# -_-.net
KiCad netlist of a schematic drawn in Altium Designer
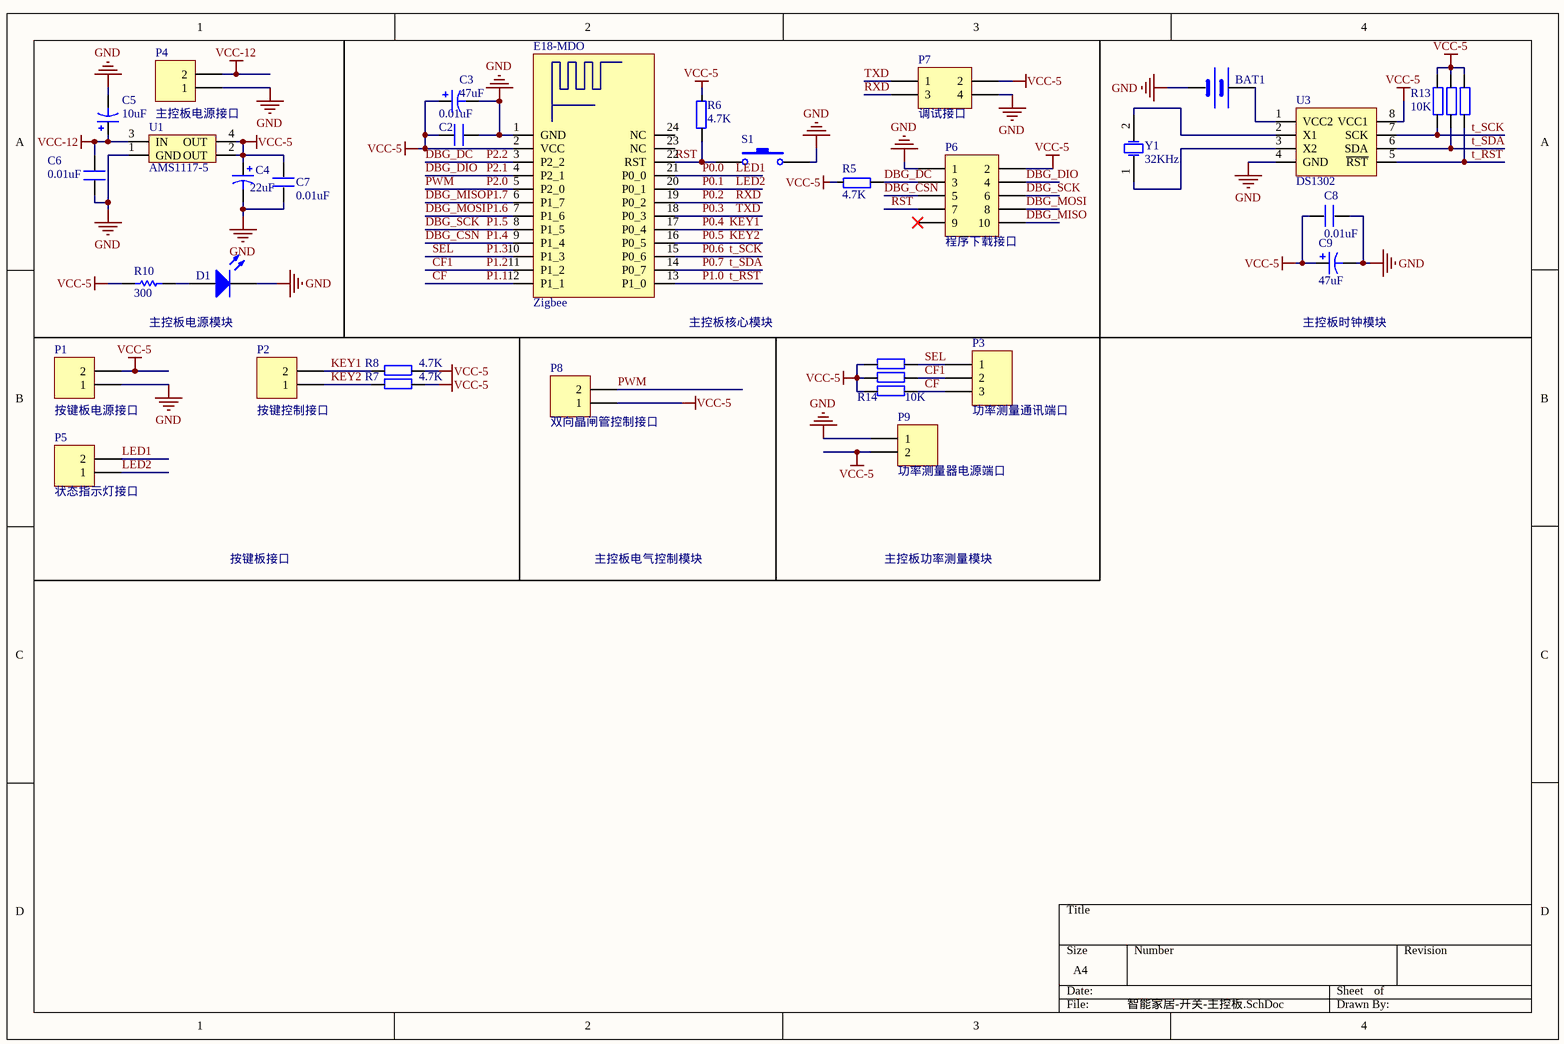
[diagram p0: 智能家居-开关-主控板.SchDoc]

(export (version "E")
  (design (tool "Eeschema 10.0.6"))
  (components
    (comp (ref "BAT1") (value "BATT") (footprint "BATM") (libsource (lib "WARSHIP") (part "BAT")))
    (comp (ref "C2") (value "0.01uF") (footprint "0.1UF") (libsource (lib "WARSHIP") (part "C")))
    (comp (ref "C3")
      (value "47uF")
      (footprint "CD5")
      (description "Polarized Capacitor (Radial)")
      (fields (field (name "Comment") "Cap Pol1") (field (name "PUBLISHER") "Altium Limited"))
      (libsource (lib "Miscellaneous Devices") (part "Cap Pol1"))
    )
    (comp (ref "C4")
      (value "22uF")
      (footprint "CD5")
      (description "Polarized Capacitor (Radial)")
      (fields (field (name "Comment") "Cap Pol1") (field (name "PUBLISHER") "Altium Limited"))
      (libsource (lib "Miscellaneous Devices") (part "Cap Pol1"))
    )
    (comp (ref "C5")
      (value "10uF")
      (footprint "CD5")
      (description "Polarized Capacitor (Radial)")
      (fields (field (name "Comment") "Cap Pol1") (field (name "PUBLISHER") "Altium Limited"))
      (libsource (lib "Miscellaneous Devices") (part "Cap Pol1"))
    )
    (comp (ref "C6") (value "0.01uF") (footprint "0.1UF") (libsource (lib "WARSHIP") (part "C")))
    (comp (ref "C7") (value "0.01uF") (footprint "0.1UF") (libsource (lib "WARSHIP") (part "C")))
    (comp (ref "C8") (value "0.01uF") (footprint "0.1UF") (libsource (lib "WARSHIP") (part "C")))
    (comp (ref "C9")
      (value "47uF")
      (footprint "CD5")
      (description "Polarized Capacitor (Radial)")
      (fields (field (name "Comment") "Cap Pol1") (field (name "PUBLISHER") "Altium Limited"))
      (libsource (lib "Miscellaneous Devices") (part "Cap Pol1"))
    )
    (comp (ref "D1")
      (value "LED0")
      (footprint "LED-3")
      (description "Typical INFRARED GaAs LED")
      (fields (field (name "PUBLISHER") "Altium Limited"))
      (libsource (lib "Miscellaneous Devices") (part "LED0"))
    )
    (comp (ref "E18-MDO")
      (value "Zigbee")
      (footprint "E18-MD0-1")
      (description "Zigbee模块")
      (libsource (lib "ESP8266V1.2") (part "E18-MDO"))
    )
    (comp (ref "P1")
      (value "按键板电源接口")
      (footprint "DG1282")
      (description "Header, 2-Pin, Right Angle")
      (fields (field (name "PUBLISHER") "Altium Limited"))
      (libsource (lib "") (part "Header 2H_1"))
    )
    (comp (ref "P2")
      (value "按键控制接口")
      (footprint "DG1282")
      (description "Header, 2-Pin, Right Angle")
      (fields (field (name "PUBLISHER") "Altium Limited"))
      (libsource (lib "") (part "Header 2H_1"))
    )
    (comp (ref "P3")
      (value "功率测量通讯端口")
      (footprint "DG1283")
      (description "Header, 3-Pin")
      (fields (field (name "PUBLISHER") "Altium Limited"))
      (libsource (lib "Miscellaneous Connectors") (part "Header 3"))
    )
    (comp (ref "P4")
      (value "主控板电源接口")
      (footprint "DG1282")
      (description "Header, 2-Pin, Right Angle")
      (fields (field (name "PUBLISHER") "Altium Limited"))
      (libsource (lib "") (part "Header 2H_1"))
    )
    (comp (ref "P5")
      (value "状态指示灯接口")
      (footprint "DG1282")
      (description "Header, 2-Pin, Right Angle")
      (fields (field (name "PUBLISHER") "Altium Limited"))
      (libsource (lib "") (part "Header 2H_1"))
    )
    (comp (ref "P6")
      (value "程序下载接口")
      (footprint "HDR2X5")
      (description "Header, 5-Pin, Dual row")
      (fields (field (name "PUBLISHER") "Altium Limited"))
      (libsource (lib "Miscellaneous Connectors") (part "Header 5X2"))
    )
    (comp (ref "P7")
      (value "调试接口")
      (footprint "HDR2X2")
      (description "Header, 2-Pin, Dual row, Right Angle")
      (fields (field (name "PUBLISHER") "Altium Limited"))
      (libsource (lib "Miscellaneous Connectors") (part "Header 2X2H"))
    )
    (comp (ref "P8")
      (value "双向晶闸管控制接口")
      (footprint "DG1282")
      (description "Header, 2-Pin, Right Angle")
      (fields (field (name "PUBLISHER") "Altium Limited"))
      (libsource (lib "") (part "Header 2H_1"))
    )
    (comp (ref "P9")
      (value "功率测量器电源端口")
      (footprint "DG1282")
      (description "Header, 2-Pin, Right Angle")
      (fields (field (name "PUBLISHER") "Altium Limited"))
      (libsource (lib "Miscellaneous Connectors") (part "Header 2H"))
    )
    (comp (ref "R5") (value "4.7K") (footprint "AXIAL-0.3") (libsource (lib "ESP8266V1.2") (part "R")))
    (comp (ref "R6") (value "4.7K") (footprint "AXIAL-0.3") (libsource (lib "ESP8266V1.2") (part "R")))
    (comp (ref "R7") (value "4.7K") (footprint "AXIAL-0.3") (libsource (lib "ESP8266V1.2") (part "R")))
    (comp (ref "R8") (value "4.7K") (footprint "AXIAL-0.3") (libsource (lib "ESP8266V1.2") (part "R")))
    (comp (ref "R10")
      (value "300")
      (footprint "AXIAL-0.3")
      (description "Resistor")
      (fields (field (name "Comment") "Res1") (field (name "PUBLISHER") "Altium Limited"))
      (libsource (lib "Miscellaneous Devices") (part "Res1"))
    )
    (comp (ref "R11") (value "10K") (footprint "AXIAL-0.3") (libsource (lib "ESP8266V1.2") (part "R")))
    (comp (ref "R12") (value "10K") (footprint "AXIAL-0.3") (libsource (lib "ESP8266V1.2") (part "R")))
    (comp (ref "R13") (value "10K") (footprint "AXIAL-0.3") (libsource (lib "ESP8266V1.2") (part "R")))
    (comp (ref "R14") (value "10K") (footprint "AXIAL-0.3") (libsource (lib "ESP8266V1.2") (part "R")))
    (comp (ref "R15") (value "10K") (footprint "AXIAL-0.3") (libsource (lib "ESP8266V1.2") (part "R")))
    (comp (ref "R16") (value "10K") (footprint "AXIAL-0.3") (libsource (lib "ESP8266V1.2") (part "R")))
    (comp (ref "S1")
      (value "SW-PB")
      (footprint "KEY_M")
      (description "Switch")
      (fields (field (name "PUBLISHER") "Altium Limited"))
      (libsource (lib "Miscellaneous Devices") (part "SW-PB"))
    )
    (comp (ref "U1") (value "AMS1117-5") (footprint "AMS1117") (libsource (lib "WARSHIP") (part "AMS1117")))
    (comp (ref "U3") (value "DS1302") (footprint "DIP-8N") (libsource (lib "杂项库") (part "DS1302")))
    (comp (ref "Y1")
      (value "32KHz")
      (footprint "3216")
      (description "Crystal Oscillator")
      (fields (field (name "PUBLISHER") "Altium Limited"))
      (libsource (lib "Miscellaneous Devices") (part "XTAL"))
    )
  )
  (nets
    (net (code "1") (name "/CF") (class "Default")
      (node (ref "E18-MDO") (pin "12") (pinfunction "P1_1_12") (pintype "passive"))
      (node (ref "P3") (pin "3") (pinfunction "3_3") (pintype "passive"))
      (node (ref "R14") (pin "1") (pintype "passive"))
    )
    (net (code "2") (name "/CF1") (class "Default")
      (node (ref "E18-MDO") (pin "11") (pinfunction "P1_2_11") (pintype "passive"))
      (node (ref "P3") (pin "2") (pinfunction "2_2") (pintype "passive"))
      (node (ref "R15") (pin "1") (pintype "passive"))
    )
    (net (code "3") (name "/DBG_CSN") (class "Default")
      (node (ref "E18-MDO") (pin "9") (pinfunction "P1_4_9") (pintype "passive"))
      (node (ref "P6") (pin "5") (pinfunction "5_5") (pintype "passive"))
    )
    (net (code "4") (name "/DBG_DC") (class "Default")
      (node (ref "E18-MDO") (pin "3") (pinfunction "P2_2_3") (pintype "passive"))
      (node (ref "P6") (pin "3") (pinfunction "3_3") (pintype "passive"))
      (node (ref "R5") (pin "2") (pintype "passive"))
    )
    (net (code "5") (name "/DBG_DIO") (class "Default")
      (node (ref "E18-MDO") (pin "4") (pinfunction "P2_1_4") (pintype "passive"))
      (node (ref "P6") (pin "4") (pinfunction "4_4") (pintype "passive"))
    )
    (net (code "6") (name "/DBG_MISO") (class "Default")
      (node (ref "E18-MDO") (pin "6") (pinfunction "P1_7_6") (pintype "passive"))
      (node (ref "P6") (pin "10") (pinfunction "10_10") (pintype "passive"))
    )
    (net (code "7") (name "/DBG_MOSI") (class "Default")
      (node (ref "E18-MDO") (pin "7") (pinfunction "P1_6_7") (pintype "passive"))
      (node (ref "P6") (pin "8") (pinfunction "8_8") (pintype "passive"))
    )
    (net (code "8") (name "/DBG_SCK") (class "Default")
      (node (ref "E18-MDO") (pin "8") (pinfunction "P1_5_8") (pintype "passive"))
      (node (ref "P6") (pin "6") (pinfunction "6_6") (pintype "passive"))
    )
    (net (code "9") (name "/KEY1") (class "Default")
      (node (ref "E18-MDO") (pin "17") (pinfunction "P0_4_17") (pintype "passive"))
      (node (ref "P2") (pin "2") (pinfunction "2_2") (pintype "passive"))
      (node (ref "R8") (pin "2") (pintype "passive"))
    )
    (net (code "10") (name "/KEY2") (class "Default")
      (node (ref "E18-MDO") (pin "16") (pinfunction "P0_5_16") (pintype "passive"))
      (node (ref "P2") (pin "1") (pinfunction "1_1") (pintype "passive"))
      (node (ref "R7") (pin "2") (pintype "passive"))
    )
    (net (code "11") (name "/LED1") (class "Default")
      (node (ref "E18-MDO") (pin "21") (pinfunction "P0_0_21") (pintype "passive"))
      (node (ref "P5") (pin "2") (pinfunction "2_2") (pintype "passive"))
    )
    (net (code "12") (name "/LED2") (class "Default")
      (node (ref "E18-MDO") (pin "20") (pinfunction "P0_1_20") (pintype "passive"))
      (node (ref "P5") (pin "1") (pinfunction "1_1") (pintype "passive"))
    )
    (net (code "13") (name "/P0.2") (class "Default")
      (node (ref "E18-MDO") (pin "19") (pinfunction "P0_2_19") (pintype "passive"))
      (node (ref "P7") (pin "3") (pinfunction "3_3") (pintype "passive"))
    )
    (net (code "14") (name "/P0.3") (class "Default")
      (node (ref "E18-MDO") (pin "18") (pinfunction "P0_3_18") (pintype "passive"))
      (node (ref "P7") (pin "1") (pinfunction "1_1") (pintype "passive"))
    )
    (net (code "15") (name "/P0.6") (class "Default")
      (node (ref "E18-MDO") (pin "15") (pinfunction "P0_6_15") (pintype "passive"))
      (node (ref "R13") (pin "1") (pintype "passive"))
      (node (ref "U3") (pin "7") (pinfunction "SCK_7") (pintype "passive"))
    )
    (net (code "16") (name "/P0.7") (class "Default")
      (node (ref "E18-MDO") (pin "14") (pinfunction "P0_7_14") (pintype "passive"))
      (node (ref "R12") (pin "1") (pintype "passive"))
      (node (ref "U3") (pin "6") (pinfunction "SDA_6") (pintype "passive"))
    )
    (net (code "17") (name "/P1.0") (class "Default")
      (node (ref "E18-MDO") (pin "13") (pinfunction "P1_0_13") (pintype "passive"))
      (node (ref "R11") (pin "1") (pintype "passive"))
      (node (ref "U3") (pin "5") (pinfunction "~{RST}_5") (pintype "passive"))
    )
    (net (code "18") (name "/P1.3") (class "Default")
      (node (ref "E18-MDO") (pin "10") (pinfunction "P1_3_10") (pintype "passive"))
      (node (ref "P3") (pin "1") (pinfunction "1_1") (pintype "passive"))
      (node (ref "R16") (pin "1") (pintype "passive"))
    )
    (net (code "19") (name "/P2.0") (class "Default")
      (node (ref "E18-MDO") (pin "5") (pinfunction "P2_0_5") (pintype "passive"))
      (node (ref "P8") (pin "2") (pinfunction "2_2") (pintype "passive"))
    )
    (net (code "20") (name "/RST") (class "Default")
      (node (ref "E18-MDO") (pin "22") (pinfunction "RST_22") (pintype "passive"))
      (node (ref "P6") (pin "7") (pinfunction "7_7") (pintype "passive"))
      (node (ref "R6") (pin "2") (pintype "passive"))
      (node (ref "S1") (pin "1") (pinfunction "1_1") (pintype "passive"))
    )
    (net (code "21") (name "GND") (class "Default")
      (node (ref "BAT1") (pin "2") (pinfunction "GND_2") (pintype "passive"))
      (node (ref "C2") (pin "2") (pintype "passive"))
      (node (ref "C3") (pin "2") (pinfunction "2_2") (pintype "passive"))
      (node (ref "C4") (pin "2") (pinfunction "2_2") (pintype "passive"))
      (node (ref "C5") (pin "2") (pinfunction "2_2") (pintype "passive"))
      (node (ref "C6") (pin "1") (pintype "passive"))
      (node (ref "C7") (pin "1") (pintype "passive"))
      (node (ref "C8") (pin "2") (pintype "passive"))
      (node (ref "C9") (pin "2") (pinfunction "2_2") (pintype "passive"))
      (node (ref "D1") (pin "2") (pinfunction "K_2") (pintype "passive"))
      (node (ref "E18-MDO") (pin "1") (pinfunction "GND_1") (pintype "passive"))
      (node (ref "P1") (pin "1") (pinfunction "1_1") (pintype "passive"))
      (node (ref "P4") (pin "1") (pinfunction "1_1") (pintype "passive"))
      (node (ref "P6") (pin "1") (pinfunction "1_1") (pintype "passive"))
      (node (ref "P7") (pin "4") (pinfunction "4_4") (pintype "passive"))
      (node (ref "P9") (pin "1") (pinfunction "1_1") (pintype "passive"))
      (node (ref "S1") (pin "2") (pinfunction "2_2") (pintype "passive"))
      (node (ref "U1") (pin "1") (pinfunction "GND_1") (pintype "passive"))
      (node (ref "U3") (pin "4") (pinfunction "GND_4") (pintype "passive"))
    )
    (net (code "22") (name "Net-(BAT1-VCC)") (class "Default")
      (node (ref "BAT1") (pin "1") (pinfunction "VCC_1") (pintype "passive"))
      (node (ref "U3") (pin "1") (pinfunction "VCC2_1") (pintype "passive"))
    )
    (net (code "23") (name "Net-(D1-A)") (class "Default")
      (node (ref "D1") (pin "1") (pinfunction "A_1") (pintype "passive"))
      (node (ref "R10") (pin "2") (pinfunction "2_2") (pintype "passive"))
    )
    (net (code "24") (name "Net-(U3-X1)") (class "Default")
      (node (ref "U3") (pin "2") (pinfunction "X1_2") (pintype "passive"))
      (node (ref "Y1") (pin "2") (pinfunction "OSC2_2") (pintype "passive"))
    )
    (net (code "25") (name "Net-(U3-X2)") (class "Default")
      (node (ref "U3") (pin "3") (pinfunction "X2_3") (pintype "passive"))
      (node (ref "Y1") (pin "1") (pinfunction "OSC1_1") (pintype "passive"))
    )
    (net (code "26") (name "VCC-5") (class "Default")
      (node (ref "C2") (pin "1") (pintype "passive"))
      (node (ref "C3") (pin "1") (pinfunction "1_1") (pintype "passive"))
      (node (ref "C4") (pin "1") (pinfunction "1_1") (pintype "passive"))
      (node (ref "C7") (pin "2") (pintype "passive"))
      (node (ref "C8") (pin "1") (pintype "passive"))
      (node (ref "C9") (pin "1") (pinfunction "1_1") (pintype "passive"))
      (node (ref "E18-MDO") (pin "2") (pinfunction "VCC_2") (pintype "passive"))
      (node (ref "P1") (pin "2") (pinfunction "2_2") (pintype "passive"))
      (node (ref "P6") (pin "2") (pinfunction "2_2") (pintype "passive"))
      (node (ref "P7") (pin "2") (pinfunction "2_2") (pintype "passive"))
      (node (ref "P8") (pin "1") (pinfunction "1_1") (pintype "passive"))
      (node (ref "P9") (pin "2") (pinfunction "2_2") (pintype "passive"))
      (node (ref "R10") (pin "1") (pinfunction "1_1") (pintype "passive"))
      (node (ref "R11") (pin "2") (pintype "passive"))
      (node (ref "R12") (pin "2") (pintype "passive"))
      (node (ref "R13") (pin "2") (pintype "passive"))
      (node (ref "R14") (pin "2") (pintype "passive"))
      (node (ref "R15") (pin "2") (pintype "passive"))
      (node (ref "R16") (pin "2") (pintype "passive"))
      (node (ref "R5") (pin "1") (pintype "passive"))
      (node (ref "R6") (pin "1") (pintype "passive"))
      (node (ref "R7") (pin "1") (pintype "passive"))
      (node (ref "R8") (pin "1") (pintype "passive"))
      (node (ref "U1") (pin "2") (pinfunction "OUT_2") (pintype "passive"))
      (node (ref "U1") (pin "4") (pinfunction "OUT_4") (pintype "passive"))
      (node (ref "U3") (pin "8") (pinfunction "VCC1_8") (pintype "passive"))
    )
    (net (code "27") (name "VCC-12") (class "Default")
      (node (ref "C5") (pin "1") (pinfunction "1_1") (pintype "passive"))
      (node (ref "C6") (pin "2") (pintype "passive"))
      (node (ref "P4") (pin "2") (pinfunction "2_2") (pintype "passive"))
      (node (ref "U1") (pin "3") (pinfunction "IN_3") (pintype "passive"))
    )
    (net (code "28") (name "unconnected-(E18-MDO-NC-Pad23)") (class "Default")
      (node (ref "E18-MDO") (pin "23") (pinfunction "NC_23") (pintype "passive"))
    )
    (net (code "29") (name "unconnected-(E18-MDO-NC-Pad24)") (class "Default")
      (node (ref "E18-MDO") (pin "24") (pinfunction "NC_24") (pintype "passive"))
    )
    (net (code "30") (name "unconnected-(P6-Pad9)") (class "Default")
      (node (ref "P6") (pin "9") (pinfunction "9_9") (pintype "passive+no_connect"))
    )
  )
)
